# Xbee_pcb.net
KiCad netlist of a schematic drawn in EAGLE
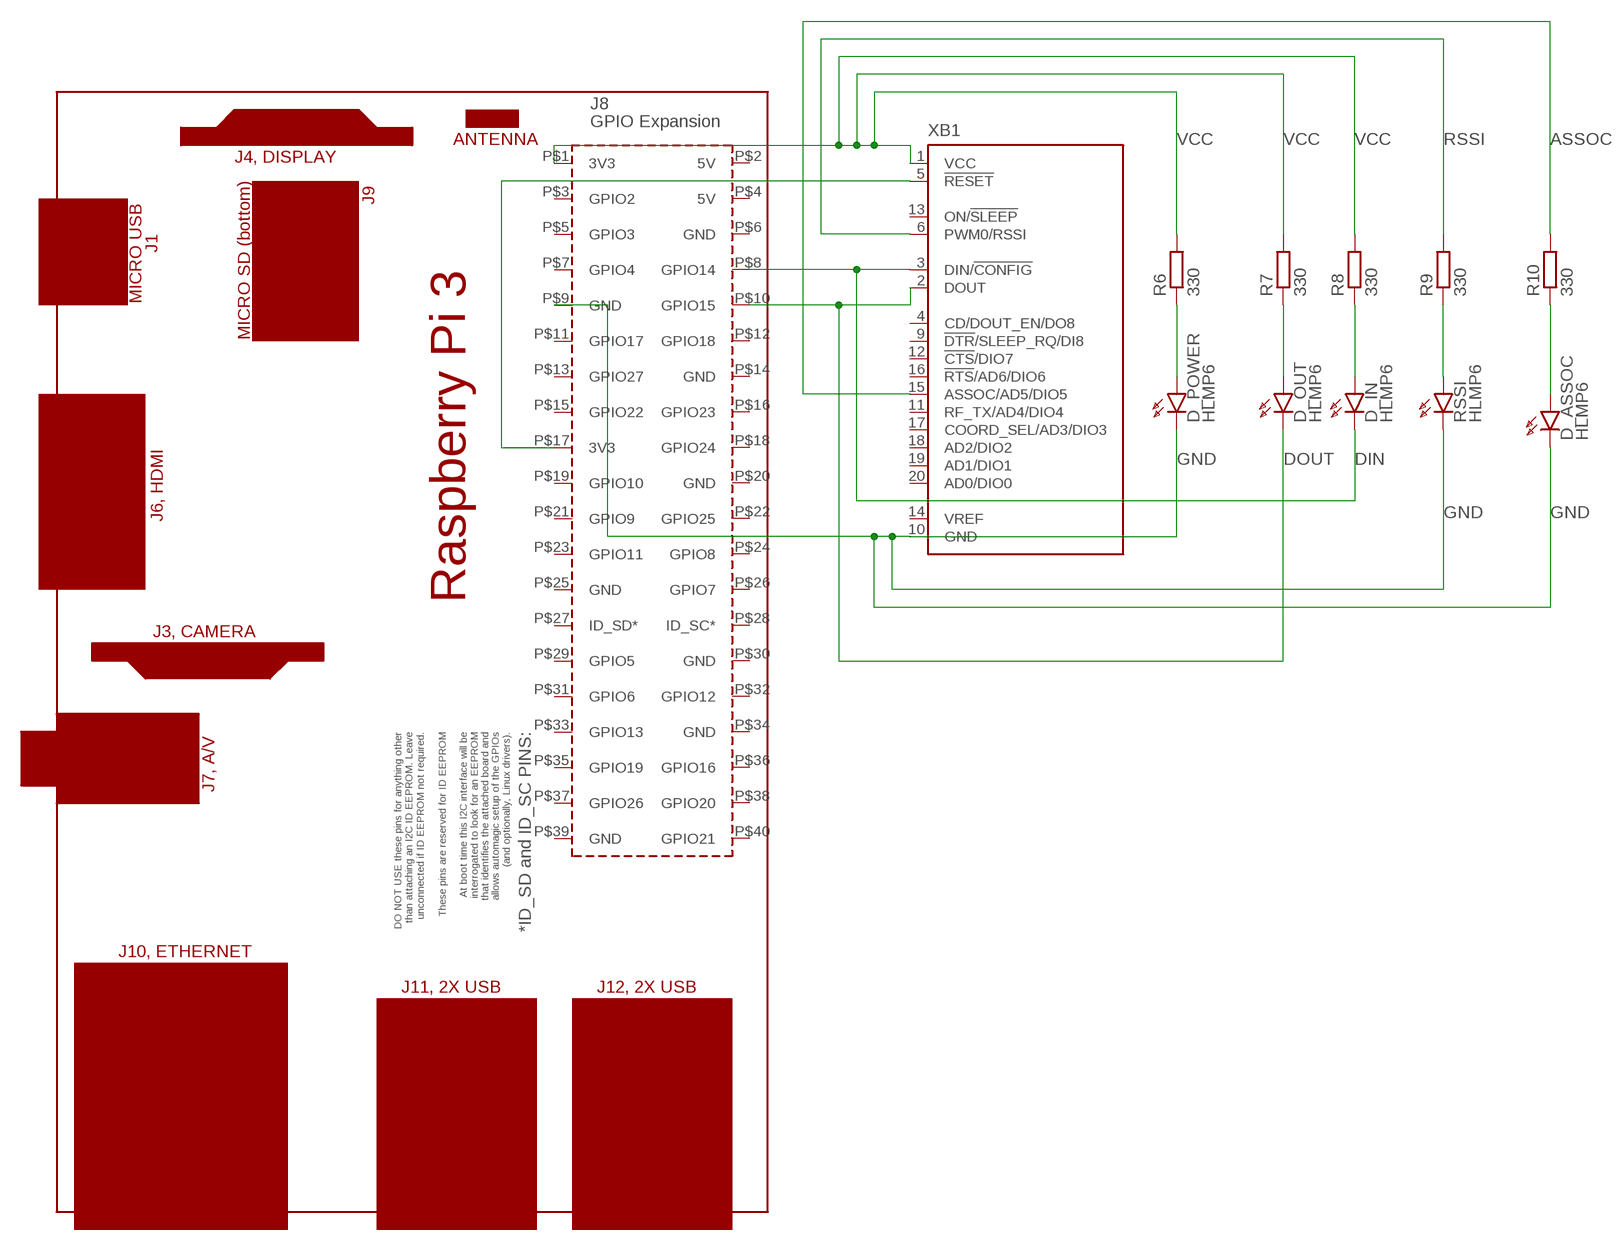
[diagram p0: schematic, sheet 1]

(export (version "E")
  (design (tool "Eeschema 10.0.6"))
  (components
    (comp (ref "D_ASSOC")
      (value "HLMP6")
      (footprint "eagle-import:HLMP6")
      (fields (field (name "MF") "AGILENT TECHNOLOGIES") (field (name "MPN") "HLMP-6500"))
      (libsource (lib "eagle-import") (part "HLMP6"))
    )
    (comp (ref "D_IN")
      (value "HLMP6")
      (footprint "eagle-import:HLMP6")
      (fields (field (name "MF") "AGILENT TECHNOLOGIES") (field (name "MPN") "HLMP-6500"))
      (libsource (lib "eagle-import") (part "HLMP6"))
    )
    (comp (ref "D_OUT")
      (value "HLMP6")
      (footprint "eagle-import:HLMP6")
      (fields (field (name "MF") "AGILENT TECHNOLOGIES") (field (name "MPN") "HLMP-6500"))
      (libsource (lib "eagle-import") (part "HLMP6"))
    )
    (comp (ref "D_POWER")
      (value "HLMP6")
      (footprint "eagle-import:HLMP6")
      (fields (field (name "MF") "AGILENT TECHNOLOGIES") (field (name "MPN") "HLMP-6500"))
      (libsource (lib "eagle-import") (part "HLMP6"))
    )
    (comp (ref "PCB1")
      (value "RPI3RPI3")
      (footprint "eagle-import:RPI3")
      (libsource (lib "eagle-import") (part "RPI3RPI3"))
    )
    (comp (ref "R6")
      (value "330")
      (footprint "eagle-import:0207_7")
      (libsource (lib "eagle-import") (part "R-EU_0207/7"))
    )
    (comp (ref "R7")
      (value "330")
      (footprint "eagle-import:0207_7")
      (libsource (lib "eagle-import") (part "R-EU_0207/7"))
    )
    (comp (ref "R8")
      (value "330")
      (footprint "eagle-import:0207_7")
      (libsource (lib "eagle-import") (part "R-EU_0207/7"))
    )
    (comp (ref "R9")
      (value "330")
      (footprint "eagle-import:0207_7")
      (libsource (lib "eagle-import") (part "R-EU_0207/7"))
    )
    (comp (ref "R10")
      (value "330")
      (footprint "eagle-import:0207_7")
      (libsource (lib "eagle-import") (part "R-EU_0207/7"))
    )
    (comp (ref "RSSI")
      (value "HLMP6")
      (footprint "eagle-import:HLMP6")
      (fields (field (name "MF") "AGILENT TECHNOLOGIES") (field (name "MPN") "HLMP-6500"))
      (libsource (lib "eagle-import") (part "HLMP6"))
    )
    (comp (ref "XB1")
      (value "XBEE")
      (footprint "eagle-import:XBEE")
      (fields (field (name "MPN") "XBP24-Z7UIT-004"))
      (libsource (lib "eagle-import") (part "XBEE"))
    )
  )
  (nets
    (net (code "1") (name "/ASSOC") (class "Default")
      (node (ref "R10") (pin "2") (pinfunction "2_2") (pintype "passive"))
      (node (ref "XB1") (pin "15") (pinfunction "ASSOC/AD5/DIO5_15") (pintype "bidirectional"))
    )
    (net (code "2") (name "/DIN") (class "Default")
      (node (ref "D_IN") (pin "K") (pinfunction "K_K") (pintype "passive"))
      (node (ref "PCB1") (pin "P$8") (pinfunction "GPIO14_P$8") (pintype "bidirectional"))
      (node (ref "XB1") (pin "3") (pinfunction "DIN/~{CONFIG}_3") (pintype "input"))
    )
    (net (code "3") (name "/DOUT") (class "Default")
      (node (ref "D_OUT") (pin "K") (pinfunction "K_K") (pintype "passive"))
      (node (ref "PCB1") (pin "P$10") (pinfunction "GPIO15_P$10") (pintype "bidirectional"))
      (node (ref "XB1") (pin "2") (pinfunction "DOUT_2") (pintype "output"))
    )
    (net (code "4") (name "/GND") (class "Default")
      (node (ref "D_ASSOC") (pin "K") (pinfunction "K_K") (pintype "passive"))
      (node (ref "D_POWER") (pin "K") (pinfunction "K_K") (pintype "passive"))
      (node (ref "PCB1") (pin "P$9") (pinfunction "GND_P$9") (pintype "bidirectional"))
      (node (ref "RSSI") (pin "K") (pinfunction "K_K") (pintype "passive"))
      (node (ref "XB1") (pin "10") (pinfunction "GND_10") (pintype "power_in"))
    )
    (net (code "5") (name "/RSSI") (class "Default")
      (node (ref "R9") (pin "2") (pinfunction "2_2") (pintype "passive"))
      (node (ref "XB1") (pin "6") (pinfunction "PWM0/RSSI_6") (pintype "output"))
    )
    (net (code "6") (name "/VCC") (class "Default")
      (node (ref "PCB1") (pin "P$1") (pinfunction "3V3_P$1") (pintype "bidirectional"))
      (node (ref "R6") (pin "2") (pinfunction "2_2") (pintype "passive"))
      (node (ref "R7") (pin "2") (pinfunction "2_2") (pintype "passive"))
      (node (ref "R8") (pin "2") (pinfunction "2_2") (pintype "passive"))
      (node (ref "XB1") (pin "1") (pinfunction "VCC_1") (pintype "power_in"))
    )
    (net (code "7") (name "Net-(D_ASSOC-PadA)") (class "Default")
      (node (ref "D_ASSOC") (pin "A") (pinfunction "A_A") (pintype "passive"))
      (node (ref "R10") (pin "1") (pinfunction "1_1") (pintype "passive"))
    )
    (net (code "8") (name "Net-(D_IN-PadA)") (class "Default")
      (node (ref "D_IN") (pin "A") (pinfunction "A_A") (pintype "passive"))
      (node (ref "R8") (pin "1") (pinfunction "1_1") (pintype "passive"))
    )
    (net (code "9") (name "Net-(D_OUT-PadA)") (class "Default")
      (node (ref "D_OUT") (pin "A") (pinfunction "A_A") (pintype "passive"))
      (node (ref "R7") (pin "1") (pinfunction "1_1") (pintype "passive"))
    )
    (net (code "10") (name "Net-(D_POWER-PadA)") (class "Default")
      (node (ref "D_POWER") (pin "A") (pinfunction "A_A") (pintype "passive"))
      (node (ref "R6") (pin "1") (pinfunction "1_1") (pintype "passive"))
    )
    (net (code "11") (name "Net-(R9-Pad1)") (class "Default")
      (node (ref "R9") (pin "1") (pinfunction "1_1") (pintype "passive"))
      (node (ref "RSSI") (pin "A") (pinfunction "A_A") (pintype "passive"))
    )
    (net (code "12") (name "Net-(XB1-~{RESET})") (class "Default")
      (node (ref "PCB1") (pin "P$17") (pinfunction "3V3_P$17") (pintype "bidirectional"))
      (node (ref "XB1") (pin "5") (pinfunction "~{RESET}_5") (pintype "input"))
    )
    (net (code "13") (name "unconnected-(PCB1-5V-PadP$2)") (class "Default")
      (node (ref "PCB1") (pin "P$2") (pinfunction "5V_P$2") (pintype "bidirectional"))
    )
    (net (code "14") (name "unconnected-(PCB1-5V-PadP$4)") (class "Default")
      (node (ref "PCB1") (pin "P$4") (pinfunction "5V_P$4") (pintype "bidirectional"))
    )
    (net (code "15") (name "unconnected-(PCB1-GND-PadP$6)") (class "Default")
      (node (ref "PCB1") (pin "P$6") (pinfunction "GND_P$6") (pintype "bidirectional"))
    )
    (net (code "16") (name "unconnected-(PCB1-GND-PadP$14)") (class "Default")
      (node (ref "PCB1") (pin "P$14") (pinfunction "GND_P$14") (pintype "bidirectional"))
    )
    (net (code "17") (name "unconnected-(PCB1-GND-PadP$20)") (class "Default")
      (node (ref "PCB1") (pin "P$20") (pinfunction "GND_P$20") (pintype "bidirectional"))
    )
    (net (code "18") (name "unconnected-(PCB1-GND-PadP$25)") (class "Default")
      (node (ref "PCB1") (pin "P$25") (pinfunction "GND_P$25") (pintype "bidirectional"))
    )
    (net (code "19") (name "unconnected-(PCB1-GND-PadP$30)") (class "Default")
      (node (ref "PCB1") (pin "P$30") (pinfunction "GND_P$30") (pintype "bidirectional"))
    )
    (net (code "20") (name "unconnected-(PCB1-GND-PadP$34)") (class "Default")
      (node (ref "PCB1") (pin "P$34") (pinfunction "GND_P$34") (pintype "bidirectional"))
    )
    (net (code "21") (name "unconnected-(PCB1-GND-PadP$39)") (class "Default")
      (node (ref "PCB1") (pin "P$39") (pinfunction "GND_P$39") (pintype "bidirectional"))
    )
    (net (code "22") (name "unconnected-(PCB1-GPIO2-PadP$3)") (class "Default")
      (node (ref "PCB1") (pin "P$3") (pinfunction "GPIO2_P$3") (pintype "bidirectional"))
    )
    (net (code "23") (name "unconnected-(PCB1-GPIO3-PadP$5)") (class "Default")
      (node (ref "PCB1") (pin "P$5") (pinfunction "GPIO3_P$5") (pintype "bidirectional"))
    )
    (net (code "24") (name "unconnected-(PCB1-GPIO4-PadP$7)") (class "Default")
      (node (ref "PCB1") (pin "P$7") (pinfunction "GPIO4_P$7") (pintype "bidirectional"))
    )
    (net (code "25") (name "unconnected-(PCB1-GPIO5-PadP$29)") (class "Default")
      (node (ref "PCB1") (pin "P$29") (pinfunction "GPIO5_P$29") (pintype "bidirectional"))
    )
    (net (code "26") (name "unconnected-(PCB1-GPIO6-PadP$31)") (class "Default")
      (node (ref "PCB1") (pin "P$31") (pinfunction "GPIO6_P$31") (pintype "bidirectional"))
    )
    (net (code "27") (name "unconnected-(PCB1-GPIO7-PadP$26)") (class "Default")
      (node (ref "PCB1") (pin "P$26") (pinfunction "GPIO7_P$26") (pintype "bidirectional"))
    )
    (net (code "28") (name "unconnected-(PCB1-GPIO8-PadP$24)") (class "Default")
      (node (ref "PCB1") (pin "P$24") (pinfunction "GPIO8_P$24") (pintype "bidirectional"))
    )
    (net (code "29") (name "unconnected-(PCB1-GPIO9-PadP$21)") (class "Default")
      (node (ref "PCB1") (pin "P$21") (pinfunction "GPIO9_P$21") (pintype "bidirectional"))
    )
    (net (code "30") (name "unconnected-(PCB1-GPIO10-PadP$19)") (class "Default")
      (node (ref "PCB1") (pin "P$19") (pinfunction "GPIO10_P$19") (pintype "bidirectional"))
    )
    (net (code "31") (name "unconnected-(PCB1-GPIO11-PadP$23)") (class "Default")
      (node (ref "PCB1") (pin "P$23") (pinfunction "GPIO11_P$23") (pintype "bidirectional"))
    )
    (net (code "32") (name "unconnected-(PCB1-GPIO12-PadP$32)") (class "Default")
      (node (ref "PCB1") (pin "P$32") (pinfunction "GPIO12_P$32") (pintype "bidirectional"))
    )
    (net (code "33") (name "unconnected-(PCB1-GPIO13-PadP$33)") (class "Default")
      (node (ref "PCB1") (pin "P$33") (pinfunction "GPIO13_P$33") (pintype "bidirectional"))
    )
    (net (code "34") (name "unconnected-(PCB1-GPIO16-PadP$36)") (class "Default")
      (node (ref "PCB1") (pin "P$36") (pinfunction "GPIO16_P$36") (pintype "bidirectional"))
    )
    (net (code "35") (name "unconnected-(PCB1-GPIO17-PadP$11)") (class "Default")
      (node (ref "PCB1") (pin "P$11") (pinfunction "GPIO17_P$11") (pintype "bidirectional"))
    )
    (net (code "36") (name "unconnected-(PCB1-GPIO18-PadP$12)") (class "Default")
      (node (ref "PCB1") (pin "P$12") (pinfunction "GPIO18_P$12") (pintype "bidirectional"))
    )
    (net (code "37") (name "unconnected-(PCB1-GPIO19-PadP$35)") (class "Default")
      (node (ref "PCB1") (pin "P$35") (pinfunction "GPIO19_P$35") (pintype "bidirectional"))
    )
    (net (code "38") (name "unconnected-(PCB1-GPIO20-PadP$38)") (class "Default")
      (node (ref "PCB1") (pin "P$38") (pinfunction "GPIO20_P$38") (pintype "bidirectional"))
    )
    (net (code "39") (name "unconnected-(PCB1-GPIO21-PadP$40)") (class "Default")
      (node (ref "PCB1") (pin "P$40") (pinfunction "GPIO21_P$40") (pintype "bidirectional"))
    )
    (net (code "40") (name "unconnected-(PCB1-GPIO22-PadP$15)") (class "Default")
      (node (ref "PCB1") (pin "P$15") (pinfunction "GPIO22_P$15") (pintype "bidirectional"))
    )
    (net (code "41") (name "unconnected-(PCB1-GPIO23-PadP$16)") (class "Default")
      (node (ref "PCB1") (pin "P$16") (pinfunction "GPIO23_P$16") (pintype "bidirectional"))
    )
    (net (code "42") (name "unconnected-(PCB1-GPIO24-PadP$18)") (class "Default")
      (node (ref "PCB1") (pin "P$18") (pinfunction "GPIO24_P$18") (pintype "bidirectional"))
    )
    (net (code "43") (name "unconnected-(PCB1-GPIO25-PadP$22)") (class "Default")
      (node (ref "PCB1") (pin "P$22") (pinfunction "GPIO25_P$22") (pintype "bidirectional"))
    )
    (net (code "44") (name "unconnected-(PCB1-GPIO26-PadP$37)") (class "Default")
      (node (ref "PCB1") (pin "P$37") (pinfunction "GPIO26_P$37") (pintype "bidirectional"))
    )
    (net (code "45") (name "unconnected-(PCB1-GPIO27-PadP$13)") (class "Default")
      (node (ref "PCB1") (pin "P$13") (pinfunction "GPIO27_P$13") (pintype "bidirectional"))
    )
    (net (code "46") (name "unconnected-(PCB1-ID_SC*-PadP$28)") (class "Default")
      (node (ref "PCB1") (pin "P$28") (pinfunction "ID_SC*_P$28") (pintype "bidirectional"))
    )
    (net (code "47") (name "unconnected-(PCB1-ID_SD*-PadP$27)") (class "Default")
      (node (ref "PCB1") (pin "P$27") (pinfunction "ID_SD*_P$27") (pintype "bidirectional"))
    )
    (net (code "48") (name "unconnected-(XB1-AD0{slash}DIO0-Pad20)") (class "Default")
      (node (ref "XB1") (pin "20") (pinfunction "AD0/DIO0_20") (pintype "bidirectional"))
    )
    (net (code "49") (name "unconnected-(XB1-AD1{slash}DIO1-Pad19)") (class "Default")
      (node (ref "XB1") (pin "19") (pinfunction "AD1/DIO1_19") (pintype "bidirectional"))
    )
    (net (code "50") (name "unconnected-(XB1-AD2{slash}DIO2-Pad18)") (class "Default")
      (node (ref "XB1") (pin "18") (pinfunction "AD2/DIO2_18") (pintype "bidirectional"))
    )
    (net (code "51") (name "unconnected-(XB1-CD{slash}DOUT_EN{slash}DO8-Pad4)") (class "Default")
      (node (ref "XB1") (pin "4") (pinfunction "CD/DOUT_EN/DO8_4") (pintype "output"))
    )
    (net (code "52") (name "unconnected-(XB1-COORD_SEL{slash}AD3{slash}DIO3-Pad17)") (class "Default")
      (node (ref "XB1") (pin "17") (pinfunction "COORD_SEL/AD3/DIO3_17") (pintype "bidirectional"))
    )
    (net (code "53") (name "unconnected-(XB1-ON{slash}~{SLEEP}-Pad13)") (class "Default")
      (node (ref "XB1") (pin "13") (pinfunction "ON/~{SLEEP}_13") (pintype "output"))
    )
    (net (code "54") (name "unconnected-(XB1-RF_TX{slash}AD4{slash}DIO4-Pad11)") (class "Default")
      (node (ref "XB1") (pin "11") (pinfunction "RF_TX/AD4/DIO4_11") (pintype "bidirectional"))
    )
    (net (code "55") (name "unconnected-(XB1-VREF-Pad14)") (class "Default")
      (node (ref "XB1") (pin "14") (pinfunction "VREF_14") (pintype "input"))
    )
    (net (code "56") (name "unconnected-(XB1-~{CTS}{slash}DIO7-Pad12)") (class "Default")
      (node (ref "XB1") (pin "12") (pinfunction "~{CTS}/DIO7_12") (pintype "bidirectional"))
    )
    (net (code "57") (name "unconnected-(XB1-~{DTR}{slash}SLEEP_RQ{slash}DI8-Pad9)") (class "Default")
      (node (ref "XB1") (pin "9") (pinfunction "~{DTR}/SLEEP_RQ/DI8_9") (pintype "bidirectional"))
    )
    (net (code "58") (name "unconnected-(XB1-~{RTS}{slash}AD6{slash}DIO6-Pad16)") (class "Default")
      (node (ref "XB1") (pin "16") (pinfunction "~{RTS}/AD6/DIO6_16") (pintype "bidirectional"))
    )
  )
)
